# P-MT3620RDB-1-0_WiFi.net
KiCad netlist of a schematic drawn in Altium Designer
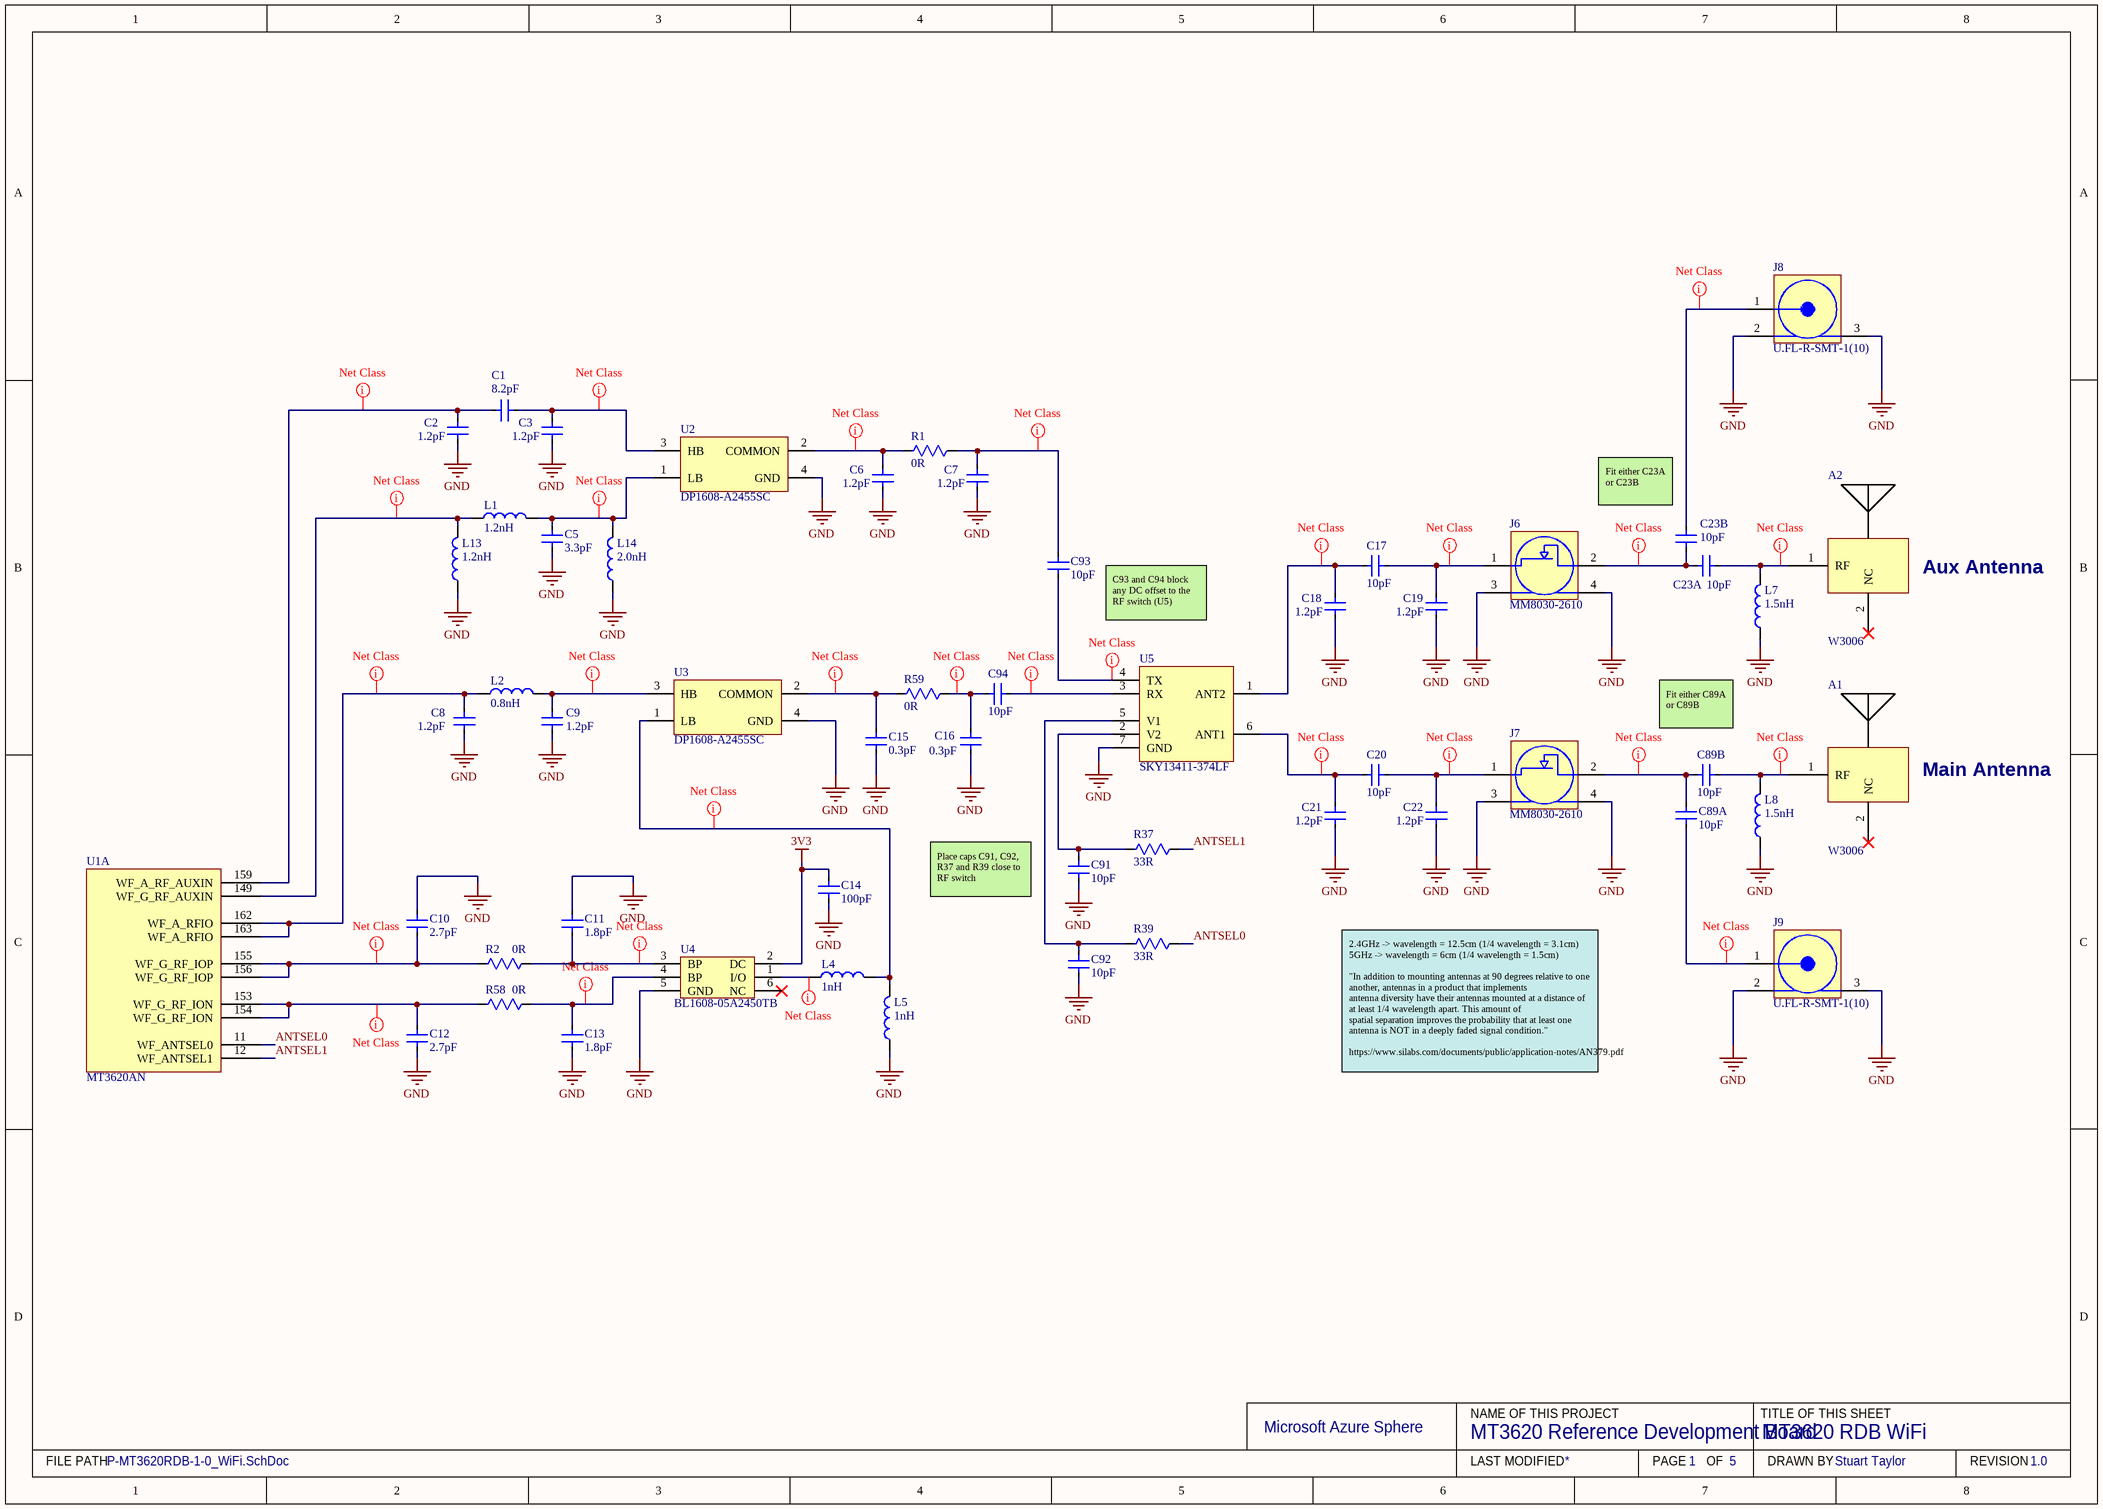
[diagram p0: P-MT3620RDB-1-0_WiFi.SchDoc]

(export (version "E")
  (design (tool "Eeschema 10.0.6"))
  (components
    (comp (ref "A1")
      (value "W3006")
      (footprint "W3006")
      (description "W3006 Chip Antenna")
      (fields (field (name "MANUFACTURER") "Pulse Electronics Corporation"))
      (libsource (lib "Pulse_W3006") (part "W3006"))
    )
    (comp (ref "A2")
      (value "W3006")
      (footprint "W3006")
      (description "W3006 Chip Antenna")
      (fields (field (name "MANUFACTURER") "Pulse Electronics Corporation"))
      (libsource (lib "Pulse_W3006") (part "W3006"))
    )
    (comp (ref "C1")
      (value "8.2pF")
      (footprint "TDK 2010")
      (description "CAP CER 8.2PF 25V NP0 0201")
      (fields
        (field (name "MANUFACTURER") "Murata")
        (field (name "MANUFACTURER PART NUMBER") "GJM0335C1E8R2CB01D")
      )
      (libsource (lib "Murata") (part "GJM0335C1E8R2CB01D"))
    )
    (comp (ref "C2")
      (value "1.2pF")
      (footprint "TDK 2010")
      (description "CAP CER 1.2PF 25V C0G 0201")
      (fields
        (field (name "MANUFACTURER") "TDK Corporation")
        (field (name "MANUFACTURER PART NUMBER") "C0603C0G1E1R2B")
      )
      (libsource (lib "TDK_Capacitor_C_0201") (part "1.2pF 0201 25V"))
    )
    (comp (ref "C3")
      (value "1.2pF")
      (footprint "TDK 2010")
      (description "CAP CER 1.2PF 25V C0G 0201")
      (fields
        (field (name "MANUFACTURER") "TDK Corporation")
        (field (name "MANUFACTURER PART NUMBER") "C0603C0G1E1R2B")
      )
      (libsource (lib "TDK_Capacitor_C_0201") (part "1.2pF 0201 25V"))
    )
    (comp (ref "C5")
      (value "3.3pF")
      (footprint "TDK 2010")
      (description "Cap Ceramic 3.3pF 25V C0G 0.25pF SMD 0201 125C T/R")
      (fields
        (field (name "MANUFACTURER") "TDK")
        (field (name "MANUFACTURER PART NUMBER") "CGA1A2C0G1E3R3C030BA")
      )
      (libsource (lib "TDK_Capacitor_C_0201") (part "3.3pF 0201 25V"))
    )
    (comp (ref "C6")
      (value "1.2pF")
      (footprint "TDK 2010")
      (description "CAP CER 1.2PF 25V C0G 0201")
      (fields
        (field (name "MANUFACTURER") "TDK Corporation")
        (field (name "MANUFACTURER PART NUMBER") "C0603C0G1E1R2B")
      )
      (libsource (lib "TDK_Capacitor_C_0201") (part "1.2pF 0201 25V"))
    )
    (comp (ref "C7")
      (value "1.2pF")
      (footprint "TDK 2010")
      (description "CAP CER 1.2PF 25V C0G 0201")
      (fields
        (field (name "MANUFACTURER") "TDK Corporation")
        (field (name "MANUFACTURER PART NUMBER") "C0603C0G1E1R2B")
      )
      (libsource (lib "TDK_Capacitor_C_0201") (part "1.2pF 0201 25V"))
    )
    (comp (ref "C8")
      (value "1.2pF")
      (footprint "TDK 2010")
      (description "CAP CER 1.2PF 25V C0G 0201")
      (fields
        (field (name "MANUFACTURER") "TDK Corporation")
        (field (name "MANUFACTURER PART NUMBER") "C0603C0G1E1R2B")
      )
      (libsource (lib "TDK_Capacitor_C_0201") (part "1.2pF 0201 25V"))
    )
    (comp (ref "C9")
      (value "1.2pF")
      (footprint "TDK 2010")
      (description "CAP CER 1.2PF 25V C0G 0201")
      (fields
        (field (name "MANUFACTURER") "TDK Corporation")
        (field (name "MANUFACTURER PART NUMBER") "C0603C0G1E1R2B")
      )
      (libsource (lib "TDK_Capacitor_C_0201") (part "1.2pF 0201 25V"))
    )
    (comp (ref "C10")
      (value "2.7pF")
      (footprint "TDK 2010")
      (description "CAP CER 2.7PF 25V C0G 0201")
      (fields (field (name "MANUFACTURER") "TDK") (field (name "MANUFACTURER PART NUMBER") "C0603C0G1E2R7B"))
      (libsource (lib "TDK_Capacitor_C_0201") (part "2.7pF 0201 25V"))
    )
    (comp (ref "C11")
      (value "1.8pF")
      (footprint "TDK 2010")
      (description "CAP CER 1.8PF 25V NP0 0201")
      (fields
        (field (name "MANUFACTURER") "Murata")
        (field (name "MANUFACTURER PART NUMBER") "GJM0335C1E1R8CB01D")
      )
      (libsource (lib "Murata") (part "GJM0335C1E1R8CB01D"))
    )
    (comp (ref "C12")
      (value "2.7pF")
      (footprint "TDK 2010")
      (description "CAP CER 2.7PF 25V C0G 0201")
      (fields (field (name "MANUFACTURER") "TDK") (field (name "MANUFACTURER PART NUMBER") "C0603C0G1E2R7B"))
      (libsource (lib "TDK_Capacitor_C_0201") (part "2.7pF 0201 25V"))
    )
    (comp (ref "C13")
      (value "1.8pF")
      (footprint "TDK 2010")
      (description "CAP CER 1.8PF 25V NP0 0201")
      (fields
        (field (name "MANUFACTURER") "Murata")
        (field (name "MANUFACTURER PART NUMBER") "GJM0335C1E1R8CB01D")
      )
      (libsource (lib "Murata") (part "GJM0335C1E1R8CB01D"))
    )
    (comp (ref "C14")
      (value "100pF")
      (footprint "CAPC1005-EIA0402 0.55MM MED")
      (description "CAP CER 100PF 50V 5% NP0 0402")
      (fields
        (field (name "MANUFACTURER") "TDK Corporation")
        (field (name "MANUFACTURER PART NUMBER") "C1005C0G1H101J050BA")
        (field (name "CAPACITANCE") "100pF")
      )
      (libsource (lib "TDK_Capacitor_C_0402") (part "100pF 0402 C0G, NP0 50V"))
    )
    (comp (ref "C15")
      (value "0.3pF")
      (footprint "TDK 2010")
      (description "CAP CER 0.3PF 25V C0G 0201")
      (fields
        (field (name "MANUFACTURER") "TDK Corporation")
        (field (name "MANUFACTURER PART NUMBER") "C0603C0G1E0R3B")
      )
      (libsource (lib "TDK_Capacitor_C_0201") (part "0.3pF 0201 25V"))
    )
    (comp (ref "C16")
      (value "0.3pF")
      (footprint "TDK 2010")
      (description "CAP CER 0.3PF 25V C0G 0201")
      (fields
        (field (name "MANUFACTURER") "TDK Corporation")
        (field (name "MANUFACTURER PART NUMBER") "C0603C0G1E0R3B")
      )
      (libsource (lib "TDK_Capacitor_C_0201") (part "0.3pF 0201 25V"))
    )
    (comp (ref "C17")
      (value "10pF")
      (footprint "TDK 2010")
      (description "CAP CER 10PF 25V C0G 0201")
      (fields
        (field (name "MANUFACTURER") "TDK Corporation")
        (field (name "MANUFACTURER PART NUMBER") "C0603C0G1E100D030BA")
      )
      (libsource (lib "TDK_Capacitor_C_0201") (part "10pF 0201 25V"))
    )
    (comp (ref "C18")
      (value "1.2pF")
      (footprint "TDK 2010")
      (description "CAP CER 1.2PF 25V C0G 0201")
      (fields
        (field (name "MANUFACTURER") "TDK Corporation")
        (field (name "MANUFACTURER PART NUMBER") "C0603C0G1E1R2B")
      )
      (libsource (lib "TDK_Capacitor_C_0201") (part "1.2pF 0201 25V"))
    )
    (comp (ref "C19")
      (value "1.2pF")
      (footprint "TDK 2010")
      (description "CAP CER 1.2PF 25V C0G 0201")
      (fields
        (field (name "MANUFACTURER") "TDK Corporation")
        (field (name "MANUFACTURER PART NUMBER") "C0603C0G1E1R2B")
      )
      (libsource (lib "TDK_Capacitor_C_0201") (part "1.2pF 0201 25V"))
    )
    (comp (ref "C20")
      (value "10pF")
      (footprint "TDK 2010")
      (description "CAP CER 10PF 25V C0G 0201")
      (fields
        (field (name "MANUFACTURER") "TDK Corporation")
        (field (name "MANUFACTURER PART NUMBER") "C0603C0G1E100D030BA")
      )
      (libsource (lib "TDK_Capacitor_C_0201") (part "10pF 0201 25V"))
    )
    (comp (ref "C21")
      (value "1.2pF")
      (footprint "TDK 2010")
      (description "CAP CER 1.2PF 25V C0G 0201")
      (fields
        (field (name "MANUFACTURER") "TDK Corporation")
        (field (name "MANUFACTURER PART NUMBER") "C0603C0G1E1R2B")
      )
      (libsource (lib "TDK_Capacitor_C_0201") (part "1.2pF 0201 25V"))
    )
    (comp (ref "C22")
      (value "1.2pF")
      (footprint "TDK 2010")
      (description "CAP CER 1.2PF 25V C0G 0201")
      (fields
        (field (name "MANUFACTURER") "TDK Corporation")
        (field (name "MANUFACTURER PART NUMBER") "C0603C0G1E1R2B")
      )
      (libsource (lib "TDK_Capacitor_C_0201") (part "1.2pF 0201 25V"))
    )
    (comp (ref "C23")
      (value "10pF")
      (footprint "CAPC1005-EIA0402 0.55MM MED - THREE WAY")
      (description "CAP CER 10PF 50V NP0 0402 - Three-way pads")
      (fields
        (field (name "MANUFACTURER") "TDK Corporation")
        (field (name "MANUFACTURER PART NUMBER") "C1005C0G1H100D050BA")
        (field (name "CAPACITANCE") "10pF")
      )
      (libsource (lib "TDK_Capacitor_C_0402") (part "10pF 0402 C0G, NP0 50V_1"))
    )
    (comp (ref "C89")
      (value "10pF")
      (footprint "CAPC1005-EIA0402 0.55MM MED - THREE WAY")
      (description "CAP CER 10PF 50V NP0 0402 - Three-way pads")
      (fields
        (field (name "MANUFACTURER") "TDK Corporation")
        (field (name "MANUFACTURER PART NUMBER") "C1005C0G1H100D050BA")
        (field (name "CAPACITANCE") "10pF")
      )
      (libsource (lib "TDK_Capacitor_C_0402") (part "10pF 0402 C0G, NP0 50V_1"))
    )
    (comp (ref "C91")
      (value "10pF")
      (footprint "TDK 2010")
      (description "CAP CER 10PF 25V C0G 0201")
      (fields
        (field (name "MANUFACTURER") "TDK Corporation")
        (field (name "MANUFACTURER PART NUMBER") "C0603C0G1E100D030BA")
      )
      (libsource (lib "TDK_Capacitor_C_0201") (part "10pF 0201 25V"))
    )
    (comp (ref "C92")
      (value "10pF")
      (footprint "TDK 2010")
      (description "CAP CER 10PF 25V C0G 0201")
      (fields
        (field (name "MANUFACTURER") "TDK Corporation")
        (field (name "MANUFACTURER PART NUMBER") "C0603C0G1E100D030BA")
      )
      (libsource (lib "TDK_Capacitor_C_0201") (part "10pF 0201 25V"))
    )
    (comp (ref "C93")
      (value "10pF")
      (footprint "TDK 2010")
      (description "CAP CER 10PF 25V C0G 0201")
      (fields
        (field (name "MANUFACTURER") "TDK Corporation")
        (field (name "MANUFACTURER PART NUMBER") "C0603C0G1E100D030BA")
      )
      (libsource (lib "TDK_Capacitor_C_0201") (part "10pF 0201 25V"))
    )
    (comp (ref "C94")
      (value "10pF")
      (footprint "TDK 2010")
      (description "CAP CER 10PF 25V C0G 0201")
      (fields
        (field (name "MANUFACTURER") "TDK Corporation")
        (field (name "MANUFACTURER PART NUMBER") "C0603C0G1E100D030BA")
      )
      (libsource (lib "TDK_Capacitor_C_0201") (part "10pF 0201 25V"))
    )
    (comp (ref "J6")
      (value "MM8030-2610")
      (footprint "MM8030-2610")
      (description "CONN UMC RECEPT SMD 2x2mm")
      (fields
        (field (name "MANUFACTURER") "Murata Electronics North America")
        (field (name "MANUFACTURER PART NUMBER") "MM8030-2610RK0")
      )
      (libsource (lib "Murata") (part "MM8030-2610"))
    )
    (comp (ref "J7")
      (value "MM8030-2610")
      (footprint "MM8030-2610")
      (description "CONN UMC RECEPT SMD 2x2mm")
      (fields
        (field (name "MANUFACTURER") "Murata Electronics North America")
        (field (name "MANUFACTURER PART NUMBER") "MM8030-2610RK0")
      )
      (libsource (lib "Murata") (part "MM8030-2610"))
    )
    (comp (ref "J8")
      (value "U.FL-R-SMT-1(10)")
      (footprint "U.FL-R-SMT-1(10)")
      (description "CONN UMC JACK STR 50 OHM SMD")
      (fields (field (name "MANUFACTURER") "Hirose Electric (HRS)"))
      (libsource (lib "Hirose") (part "U.FL-R-SMT-1(10)"))
    )
    (comp (ref "J9")
      (value "U.FL-R-SMT-1(10)")
      (footprint "U.FL-R-SMT-1(10)")
      (description "CONN UMC JACK STR 50 OHM SMD")
      (fields (field (name "MANUFACTURER") "Hirose Electric (HRS)"))
      (libsource (lib "Hirose") (part "U.FL-R-SMT-1(10)"))
    )
    (comp (ref "L1")
      (value "1.2nH")
      (footprint "TDK 2010")
      (description "FIXED IND 1.2NH 1A 80 MOHM SMD")
      (fields
        (field (name "MANUFACTURER") "TDK")
        (field (name "MANUFACTURER PART NUMBER") "MHQ0603P1N2CT000")
      )
      (libsource (lib "TDK") (part "1.2nH 0201"))
    )
    (comp (ref "L2")
      (value "0.8nH")
      (footprint "TDK 2010")
      (description "FIXED IND 0.8NH 1A 70 MOHM SMD")
      (fields
        (field (name "MANUFACTURER") "TDK Corporation")
        (field (name "MANUFACTURER PART NUMBER") "MHQ0603P0N8CT000")
      )
      (libsource (lib "TDK") (part "0.8nH 0201"))
    )
    (comp (ref "L4")
      (value "1nH")
      (footprint "TDK 2010")
      (description "FIXED IND 1NH 1A 70 MOHM SMD")
      (fields
        (field (name "MANUFACTURER") "TDK Corporation")
        (field (name "MANUFACTURER PART NUMBER") "MHQ0603P1N0CT000")
      )
      (libsource (lib "TDK") (part "1nH 0201"))
    )
    (comp (ref "L5")
      (value "1nH")
      (footprint "TDK 2010")
      (description "FIXED IND 1NH 1A 70 MOHM SMD")
      (fields
        (field (name "MANUFACTURER") "TDK Corporation")
        (field (name "MANUFACTURER PART NUMBER") "MHQ0603P1N0CT000")
      )
      (libsource (lib "TDK") (part "1nH 0201"))
    )
    (comp (ref "L7")
      (value "1.5nH")
      (footprint "TDK 2010")
      (description "MURATA - LQP03TN1N5B02D - INDUCTOR, 1.5NH, 0.6A, 0.1NH, 15GHZ")
      (fields
        (field (name "MANUFACTURER") "MURATA")
        (field (name "MANUFACTURER PART NUMBER") "LQP03TN1N5B02D")
      )
      (libsource (lib "Murata") (part "LQP03TN1N5B02D"))
    )
    (comp (ref "L8")
      (value "1.5nH")
      (footprint "TDK 2010")
      (description "MURATA - LQP03TN1N5B02D - INDUCTOR, 1.5NH, 0.6A, 0.1NH, 15GHZ")
      (fields
        (field (name "MANUFACTURER") "MURATA")
        (field (name "MANUFACTURER PART NUMBER") "LQP03TN1N5B02D")
      )
      (libsource (lib "Murata") (part "LQP03TN1N5B02D"))
    )
    (comp (ref "L13")
      (value "1.2nH")
      (footprint "TDK 2010")
      (description "FIXED IND 1.2NH 1A 80 MOHM SMD")
      (fields
        (field (name "MANUFACTURER") "TDK")
        (field (name "MANUFACTURER PART NUMBER") "MHQ0603P1N2CT000")
      )
      (libsource (lib "TDK") (part "1.2nH 0201"))
    )
    (comp (ref "L14")
      (value "2.0nH")
      (footprint "TDK 2010")
      (description "FIXED IND 2NH 700MA 120 MOHM SMD")
      (fields
        (field (name "MANUFACTURER") "TDK")
        (field (name "MANUFACTURER PART NUMBER") "MHQ0603P2N0CT000")
      )
      (libsource (lib "TDK") (part "2.0nH 0201"))
    )
    (comp (ref "R1")
      (value "0R")
      (footprint "TDK 2010")
      (description "RES SMD 0.0OHM JUMPER 1/20W 0201")
      (fields
        (field (name "MANUFACTURER") "Panasonic Electronic Components")
        (field (name "MANUFACTURER PART NUMBER") "ERJ-1GN0R00C")
      )
      (libsource (lib "Panasonic_Resistor_ERJ1GN") (part "0R 0201"))
    )
    (comp (ref "R2")
      (value "0R")
      (footprint "TDK 2010")
      (description "RES SMD 0.0OHM JUMPER 1/20W 0201")
      (fields
        (field (name "MANUFACTURER") "Panasonic Electronic Components")
        (field (name "MANUFACTURER PART NUMBER") "ERJ-1GN0R00C")
      )
      (libsource (lib "Panasonic_Resistor_ERJ1GN") (part "0R 0201"))
    )
    (comp (ref "R37")
      (value "33R")
      (footprint "RES 0402 MEDIUM DENSITY")
      (description "RES 33 OHM 1/10W 1% 0402 SMD")
      (fields
        (field (name "MANUFACTURER") "Panasonic Electronic Components")
        (field (name "MANUFACTURER PART NUMBER") "ERJ-2RKF33R0X")
        (field (name "RESISTANCE (OHMS)") "33R")
      )
      (libsource (lib "Panasonic_Resistor_ERJ2R") (part "33R"))
    )
    (comp (ref "R39")
      (value "33R")
      (footprint "RES 0402 MEDIUM DENSITY")
      (description "RES 33 OHM 1/10W 1% 0402 SMD")
      (fields
        (field (name "MANUFACTURER") "Panasonic Electronic Components")
        (field (name "MANUFACTURER PART NUMBER") "ERJ-2RKF33R0X")
        (field (name "RESISTANCE (OHMS)") "33R")
      )
      (libsource (lib "Panasonic_Resistor_ERJ2R") (part "33R"))
    )
    (comp (ref "R58")
      (value "0R")
      (footprint "TDK 2010")
      (description "RES SMD 0.0OHM JUMPER 1/20W 0201")
      (fields
        (field (name "MANUFACTURER") "Panasonic Electronic Components")
        (field (name "MANUFACTURER PART NUMBER") "ERJ-1GN0R00C")
      )
      (libsource (lib "Panasonic_Resistor_ERJ1GN") (part "0R 0201"))
    )
    (comp (ref "R59")
      (value "0R")
      (footprint "TDK 2010")
      (description "RES SMD 0.0OHM JUMPER 1/20W 0201")
      (fields
        (field (name "MANUFACTURER") "Panasonic Electronic Components")
        (field (name "MANUFACTURER PART NUMBER") "ERJ-1GN0R00C")
      )
      (libsource (lib "Panasonic_Resistor_ERJ1GN") (part "0R 0201"))
    )
    (comp (ref "U1")
      (value "MT3620AN")
      (footprint "Mt.Blanca")
      (libsource (lib "Microsoft") (part "MT3620AN"))
    )
    (comp (ref "U2")
      (value "DP1608-A2455SC")
      (footprint "DP1608-A2455SC")
      (description "Diplexer")
      (libsource (lib "ACX") (part "DP1608-A2455SC"))
    )
    (comp (ref "U3")
      (value "DP1608-A2455SC")
      (footprint "DP1608-A2455SC")
      (description "Diplexer")
      (libsource (lib "ACX") (part "DP1608-A2455SC"))
    )
    (comp (ref "U4")
      (value "BL1608-05A2450TB")
      (footprint "BL1608-05A2450TB")
      (description "Balun")
      (libsource (lib "ACX") (part "BL1608-05A2450TB"))
    )
    (comp (ref "U5")
      (value "SKY13411-374LF")
      (footprint "SKY13411-374LF")
      (description "RF SWITCH")
      (fields (field (name "MANUFACTURER") "Skyworks Solutions Inc."))
      (libsource (lib "Skyworks") (part "SKY13411-374LF"))
    )
  )
  (nets
    (net (code "1") (name "/ANTSEL0") (class "Default")
      (node (ref "R39") (pin "1") (pinfunction "1_1") (pintype "passive"))
      (node (ref "U1") (pin "11") (pinfunction "WF_ANTSEL0_11") (pintype "passive"))
    )
    (net (code "2") (name "/ANTSEL1") (class "Default")
      (node (ref "R37") (pin "1") (pinfunction "1_1") (pintype "passive"))
      (node (ref "U1") (pin "12") (pinfunction "WF_ANTSEL1_12") (pintype "passive"))
    )
    (net (code "3") (name "3V3") (class "Default")
      (node (ref "C14") (pin "2") (pinfunction "2_2") (pintype "passive"))
      (node (ref "U4") (pin "2") (pinfunction "DC_2") (pintype "passive"))
    )
    (net (code "4") (name "GND") (class "Default")
      (node (ref "C10") (pin "2") (pinfunction "2_2") (pintype "passive"))
      (node (ref "C11") (pin "2") (pinfunction "2_2") (pintype "passive"))
      (node (ref "C12") (pin "1") (pinfunction "1_1") (pintype "passive"))
      (node (ref "C13") (pin "1") (pinfunction "1_1") (pintype "passive"))
      (node (ref "C14") (pin "1") (pinfunction "1_1") (pintype "passive"))
      (node (ref "C15") (pin "1") (pinfunction "1_1") (pintype "passive"))
      (node (ref "C16") (pin "1") (pinfunction "1_1") (pintype "passive"))
      (node (ref "C18") (pin "1") (pinfunction "1_1") (pintype "passive"))
      (node (ref "C19") (pin "1") (pinfunction "1_1") (pintype "passive"))
      (node (ref "C2") (pin "1") (pinfunction "1_1") (pintype "passive"))
      (node (ref "C21") (pin "1") (pinfunction "1_1") (pintype "passive"))
      (node (ref "C22") (pin "1") (pinfunction "1_1") (pintype "passive"))
      (node (ref "C3") (pin "1") (pinfunction "1_1") (pintype "passive"))
      (node (ref "C5") (pin "1") (pinfunction "1_1") (pintype "passive"))
      (node (ref "C6") (pin "1") (pinfunction "1_1") (pintype "passive"))
      (node (ref "C7") (pin "1") (pinfunction "1_1") (pintype "passive"))
      (node (ref "C8") (pin "1") (pinfunction "1_1") (pintype "passive"))
      (node (ref "C9") (pin "1") (pinfunction "1_1") (pintype "passive"))
      (node (ref "C91") (pin "1") (pinfunction "1_1") (pintype "passive"))
      (node (ref "C92") (pin "1") (pinfunction "1_1") (pintype "passive"))
      (node (ref "J6") (pin "3") (pinfunction "GND_3") (pintype "passive"))
      (node (ref "J6") (pin "4") (pinfunction "GND_4") (pintype "passive"))
      (node (ref "J7") (pin "3") (pinfunction "GND_3") (pintype "passive"))
      (node (ref "J7") (pin "4") (pinfunction "GND_4") (pintype "passive"))
      (node (ref "J8") (pin "2") (pinfunction "GND_2") (pintype "passive"))
      (node (ref "J8") (pin "3") (pinfunction "GND_3") (pintype "passive"))
      (node (ref "J9") (pin "2") (pinfunction "GND_2") (pintype "passive"))
      (node (ref "J9") (pin "3") (pinfunction "GND_3") (pintype "passive"))
      (node (ref "L13") (pin "1") (pinfunction "1_1") (pintype "passive"))
      (node (ref "L14") (pin "1") (pinfunction "1_1") (pintype "passive"))
      (node (ref "L5") (pin "1") (pinfunction "1_1") (pintype "passive"))
      (node (ref "L7") (pin "1") (pinfunction "1_1") (pintype "passive"))
      (node (ref "L8") (pin "1") (pinfunction "1_1") (pintype "passive"))
      (node (ref "U2") (pin "4") (pinfunction "GND_4") (pintype "passive"))
      (node (ref "U3") (pin "4") (pinfunction "GND_4") (pintype "passive"))
      (node (ref "U4") (pin "5") (pinfunction "GND_5") (pintype "passive"))
      (node (ref "U5") (pin "7") (pinfunction "GND_7") (pintype "passive"))
    )
    (net (code "5") (name "Net-(A1-RF)") (class "Default")
      (node (ref "A1") (pin "1") (pinfunction "RF_1") (pintype "passive"))
      (node (ref "C89") (pin "3") (pinfunction "3_3") (pintype "passive"))
      (node (ref "L8") (pin "2") (pinfunction "2_2") (pintype "passive"))
    )
    (net (code "6") (name "Net-(A2-RF)") (class "Default")
      (node (ref "A2") (pin "1") (pinfunction "RF_1") (pintype "passive"))
      (node (ref "C23") (pin "2") (pinfunction "2_2") (pintype "passive"))
      (node (ref "L7") (pin "2") (pinfunction "2_2") (pintype "passive"))
    )
    (net (code "7") (name "Net-(C7-Pad2)") (class "Default")
      (node (ref "C7") (pin "2") (pinfunction "2_2") (pintype "passive"))
      (node (ref "C93") (pin "2") (pinfunction "2_2") (pintype "passive"))
      (node (ref "R1") (pin "1") (pinfunction "1_1") (pintype "passive"))
    )
    (net (code "8") (name "Net-(C8-Pad2)") (class "Default")
      (node (ref "C8") (pin "2") (pinfunction "2_2") (pintype "passive"))
      (node (ref "L2") (pin "1") (pinfunction "1_1") (pintype "passive"))
      (node (ref "U1") (pin "162") (pinfunction "WF_A_RFIO_162") (pintype "passive"))
      (node (ref "U1") (pin "163") (pinfunction "WF_A_RFIO_163") (pintype "passive"))
    )
    (net (code "9") (name "Net-(C10-Pad1)") (class "Default")
      (node (ref "C10") (pin "1") (pinfunction "1_1") (pintype "passive"))
      (node (ref "R2") (pin "2") (pinfunction "2_2") (pintype "passive"))
      (node (ref "U1") (pin "155") (pinfunction "WF_G_RF_IOP_155") (pintype "passive"))
      (node (ref "U1") (pin "156") (pinfunction "WF_G_RF_IOP_156") (pintype "passive"))
    )
    (net (code "10") (name "Net-(C11-Pad1)") (class "Default")
      (node (ref "C11") (pin "1") (pinfunction "1_1") (pintype "passive"))
      (node (ref "R2") (pin "1") (pinfunction "1_1") (pintype "passive"))
      (node (ref "U4") (pin "3") (pinfunction "BP_3") (pintype "passive"))
    )
    (net (code "11") (name "Net-(C12-Pad2)") (class "Default")
      (node (ref "C12") (pin "2") (pinfunction "2_2") (pintype "passive"))
      (node (ref "R58") (pin "2") (pinfunction "2_2") (pintype "passive"))
      (node (ref "U1") (pin "153") (pinfunction "WF_G_RF_ION_153") (pintype "passive"))
      (node (ref "U1") (pin "154") (pinfunction "WF_G_RF_ION_154") (pintype "passive"))
    )
    (net (code "12") (name "Net-(C13-Pad2)") (class "Default")
      (node (ref "C13") (pin "2") (pinfunction "2_2") (pintype "passive"))
      (node (ref "R58") (pin "1") (pinfunction "1_1") (pintype "passive"))
      (node (ref "U4") (pin "4") (pinfunction "BP_4") (pintype "passive"))
    )
    (net (code "13") (name "Net-(C16-Pad2)") (class "Default")
      (node (ref "C16") (pin "2") (pinfunction "2_2") (pintype "passive"))
      (node (ref "C94") (pin "2") (pinfunction "2_2") (pintype "passive"))
      (node (ref "R59") (pin "1") (pinfunction "1_1") (pintype "passive"))
    )
    (net (code "14") (name "Net-(J6-IN)") (class "Default")
      (node (ref "C17") (pin "2") (pinfunction "2_2") (pintype "passive"))
      (node (ref "C19") (pin "2") (pinfunction "2_2") (pintype "passive"))
      (node (ref "J6") (pin "1") (pinfunction "IN_1") (pintype "passive"))
    )
    (net (code "15") (name "Net-(J6-OUT)") (class "Default")
      (node (ref "C23") (pin "1") (pinfunction "1_1") (pintype "passive"))
      (node (ref "J6") (pin "2") (pinfunction "OUT_2") (pintype "passive"))
    )
    (net (code "16") (name "Net-(J7-IN)") (class "Default")
      (node (ref "C20") (pin "2") (pinfunction "2_2") (pintype "passive"))
      (node (ref "C22") (pin "2") (pinfunction "2_2") (pintype "passive"))
      (node (ref "J7") (pin "1") (pinfunction "IN_1") (pintype "passive"))
    )
    (net (code "17") (name "Net-(J7-OUT)") (class "Default")
      (node (ref "C89") (pin "1") (pinfunction "1_1") (pintype "passive"))
      (node (ref "J7") (pin "2") (pinfunction "OUT_2") (pintype "passive"))
    )
    (net (code "18") (name "Net-(J8-IN)") (class "Default")
      (node (ref "C23") (pin "3") (pinfunction "3_3") (pintype "passive"))
      (node (ref "J8") (pin "1") (pinfunction "IN_1") (pintype "passive"))
    )
    (net (code "19") (name "Net-(J9-IN)") (class "Default")
      (node (ref "C89") (pin "2") (pinfunction "2_2") (pintype "passive"))
      (node (ref "J9") (pin "1") (pinfunction "IN_1") (pintype "passive"))
    )
    (net (code "20") (name "Net-(U1A-WF_A_RF_AUXIN)") (class "Default")
      (node (ref "C1") (pin "1") (pinfunction "1_1") (pintype "passive"))
      (node (ref "C2") (pin "2") (pinfunction "2_2") (pintype "passive"))
      (node (ref "U1") (pin "159") (pinfunction "WF_A_RF_AUXIN_159") (pintype "passive"))
    )
    (net (code "21") (name "Net-(U1A-WF_G_RF_AUXIN)") (class "Default")
      (node (ref "L1") (pin "1") (pinfunction "1_1") (pintype "passive"))
      (node (ref "L13") (pin "2") (pinfunction "2_2") (pintype "passive"))
      (node (ref "U1") (pin "149") (pinfunction "WF_G_RF_AUXIN_149") (pintype "passive"))
    )
    (net (code "22") (name "Net-(U2-COMMON)") (class "Default")
      (node (ref "C6") (pin "2") (pinfunction "2_2") (pintype "passive"))
      (node (ref "R1") (pin "2") (pinfunction "2_2") (pintype "passive"))
      (node (ref "U2") (pin "2") (pinfunction "COMMON_2") (pintype "passive"))
    )
    (net (code "23") (name "Net-(U2-HB)") (class "Default")
      (node (ref "C1") (pin "2") (pinfunction "2_2") (pintype "passive"))
      (node (ref "C3") (pin "2") (pinfunction "2_2") (pintype "passive"))
      (node (ref "U2") (pin "3") (pinfunction "HB_3") (pintype "passive"))
    )
    (net (code "24") (name "Net-(U2-LB)") (class "Default")
      (node (ref "C5") (pin "2") (pinfunction "2_2") (pintype "passive"))
      (node (ref "L1") (pin "2") (pinfunction "2_2") (pintype "passive"))
      (node (ref "L14") (pin "2") (pinfunction "2_2") (pintype "passive"))
      (node (ref "U2") (pin "1") (pinfunction "LB_1") (pintype "passive"))
    )
    (net (code "25") (name "Net-(U3-COMMON)") (class "Default")
      (node (ref "C15") (pin "2") (pinfunction "2_2") (pintype "passive"))
      (node (ref "R59") (pin "2") (pinfunction "2_2") (pintype "passive"))
      (node (ref "U3") (pin "2") (pinfunction "COMMON_2") (pintype "passive"))
    )
    (net (code "26") (name "Net-(U3-HB)") (class "Default")
      (node (ref "C9") (pin "2") (pinfunction "2_2") (pintype "passive"))
      (node (ref "L2") (pin "2") (pinfunction "2_2") (pintype "passive"))
      (node (ref "U3") (pin "3") (pinfunction "HB_3") (pintype "passive"))
    )
    (net (code "27") (name "Net-(U3-LB)") (class "Default")
      (node (ref "L4") (pin "2") (pinfunction "2_2") (pintype "passive"))
      (node (ref "L5") (pin "2") (pinfunction "2_2") (pintype "passive"))
      (node (ref "U3") (pin "1") (pinfunction "LB_1") (pintype "passive"))
    )
    (net (code "28") (name "Net-(U4-I{slash}O)") (class "Default")
      (node (ref "L4") (pin "1") (pinfunction "1_1") (pintype "passive"))
      (node (ref "U4") (pin "1") (pinfunction "I/O_1") (pintype "passive"))
    )
    (net (code "29") (name "Net-(U5-ANT1)") (class "Default")
      (node (ref "C20") (pin "1") (pinfunction "1_1") (pintype "passive"))
      (node (ref "C21") (pin "2") (pinfunction "2_2") (pintype "passive"))
      (node (ref "U5") (pin "6") (pinfunction "ANT1_6") (pintype "passive"))
    )
    (net (code "30") (name "Net-(U5-ANT2)") (class "Default")
      (node (ref "C17") (pin "1") (pinfunction "1_1") (pintype "passive"))
      (node (ref "C18") (pin "2") (pinfunction "2_2") (pintype "passive"))
      (node (ref "U5") (pin "1") (pinfunction "ANT2_1") (pintype "passive"))
    )
    (net (code "31") (name "Net-(U5-RX)") (class "Default")
      (node (ref "C94") (pin "1") (pinfunction "1_1") (pintype "passive"))
      (node (ref "U5") (pin "3") (pinfunction "RX_3") (pintype "passive"))
    )
    (net (code "32") (name "Net-(U5-TX)") (class "Default")
      (node (ref "C93") (pin "1") (pinfunction "1_1") (pintype "passive"))
      (node (ref "U5") (pin "4") (pinfunction "TX_4") (pintype "passive"))
    )
    (net (code "33") (name "Net-(U5-V1)") (class "Default")
      (node (ref "C92") (pin "2") (pinfunction "2_2") (pintype "passive"))
      (node (ref "R39") (pin "2") (pinfunction "2_2") (pintype "passive"))
      (node (ref "U5") (pin "5") (pinfunction "V1_5") (pintype "passive"))
    )
    (net (code "34") (name "Net-(U5-V2)") (class "Default")
      (node (ref "C91") (pin "2") (pinfunction "2_2") (pintype "passive"))
      (node (ref "R37") (pin "2") (pinfunction "2_2") (pintype "passive"))
      (node (ref "U5") (pin "2") (pinfunction "V2_2") (pintype "passive"))
    )
    (net (code "35") (name "unconnected-(A1-NC-Pad2)") (class "Default")
      (node (ref "A1") (pin "2") (pinfunction "NC_2") (pintype "passive+no_connect"))
    )
    (net (code "36") (name "unconnected-(A2-NC-Pad2)") (class "Default")
      (node (ref "A2") (pin "2") (pinfunction "NC_2") (pintype "passive+no_connect"))
    )
    (net (code "37") (name "unconnected-(U4-NC-Pad6)") (class "Default")
      (node (ref "U4") (pin "6") (pinfunction "NC_6") (pintype "passive+no_connect"))
    )
  )
)
